# Power_Cell_Lipo_Charger_Booster.net
KiCad netlist of a schematic drawn in EAGLE
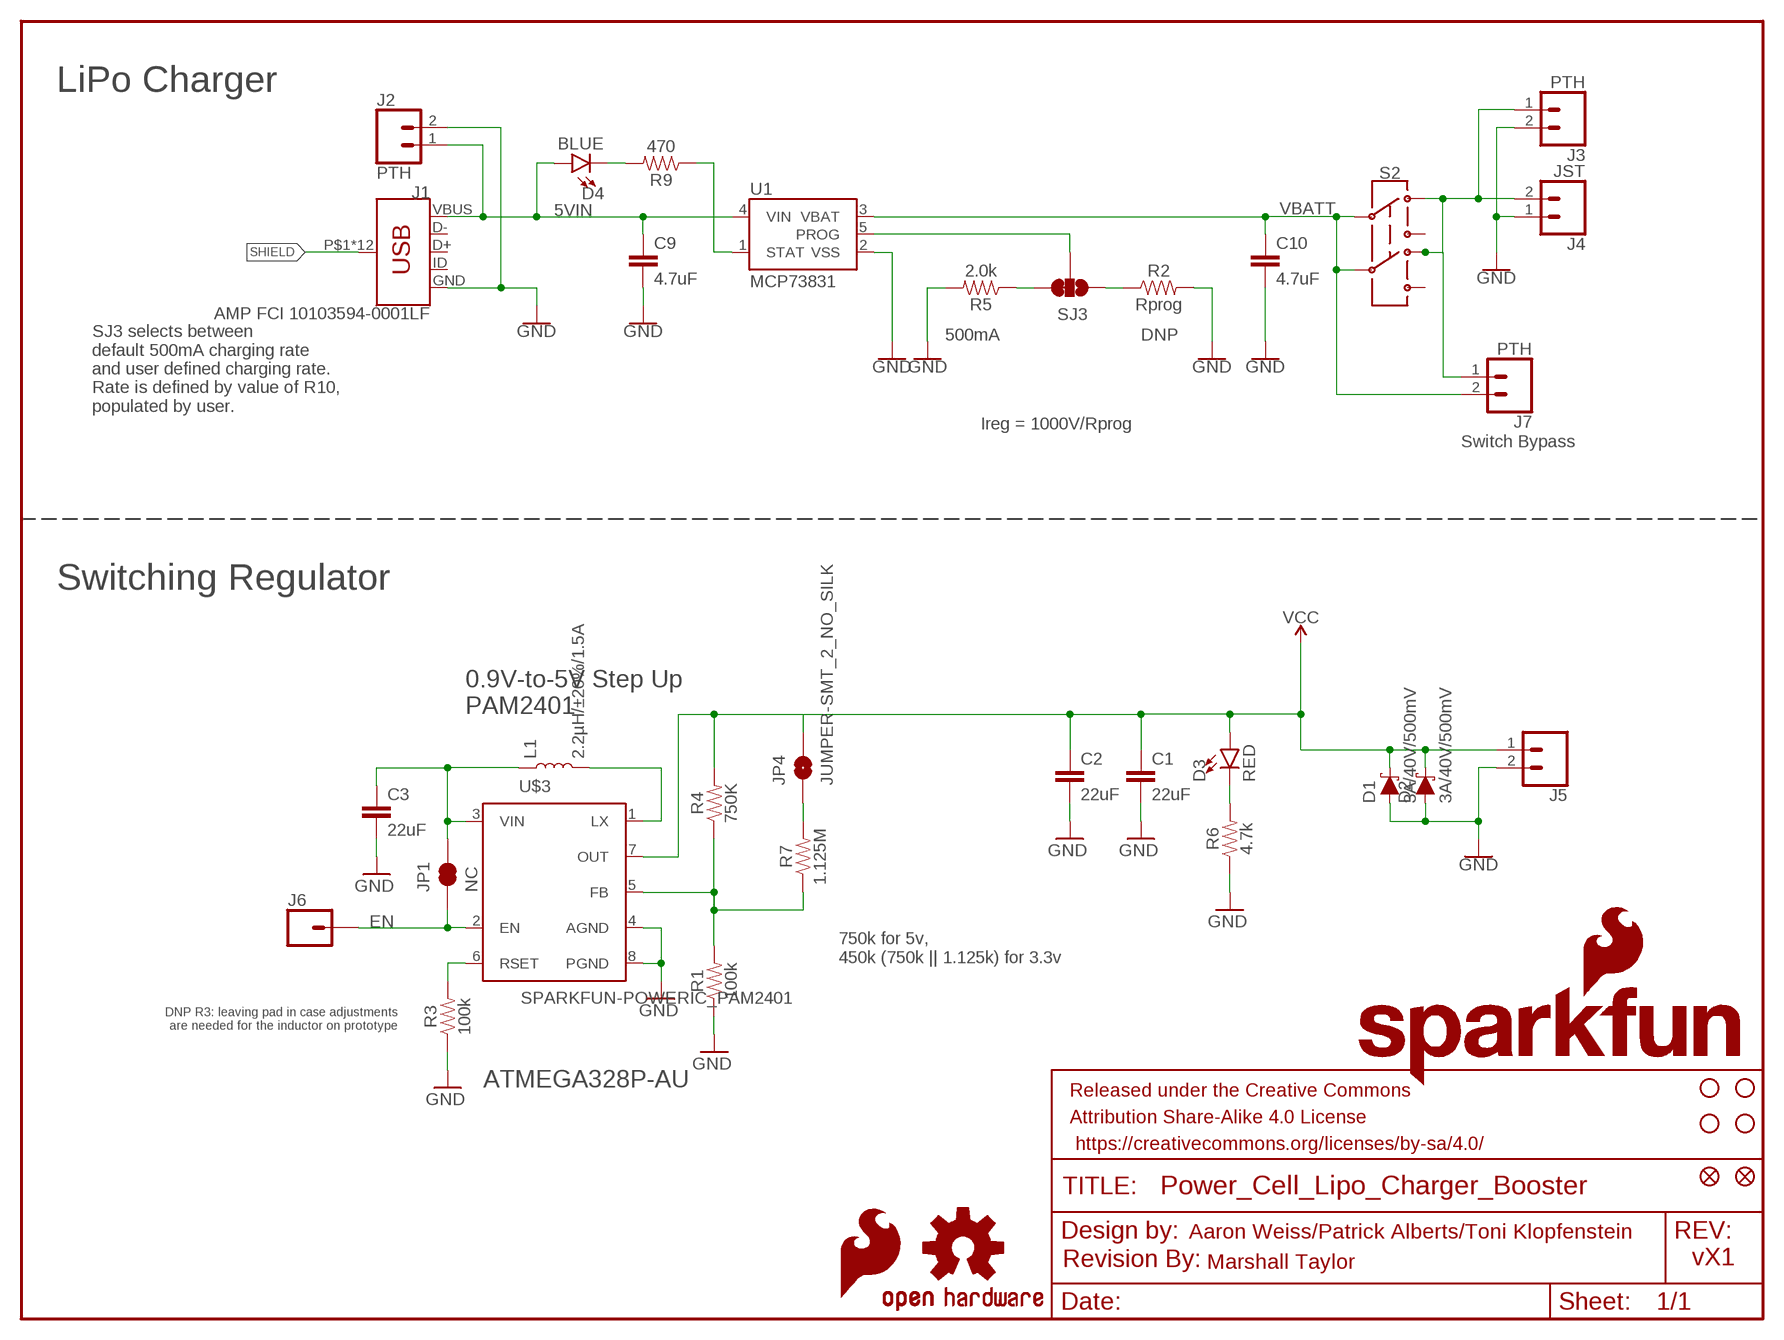
[diagram p0: schematic, sheet 1]

(export (version "E")
  (design (tool "Eeschema 10.0.6"))
  (components
    (comp (ref "C1")
      (value "22uF")
      (footprint "eagle-import:0805")
      (libsource (lib "eagle-import") (part "22UF-0805-6.3V-20%"))
    )
    (comp (ref "C2")
      (value "22uF")
      (footprint "eagle-import:0805")
      (libsource (lib "eagle-import") (part "22UF-0805-6.3V-20%"))
    )
    (comp (ref "C3")
      (value "22uF")
      (footprint "eagle-import:0805")
      (libsource (lib "eagle-import") (part "22UF-0805-6.3V-20%"))
    )
    (comp (ref "C9")
      (value "4.7uF")
      (footprint "eagle-import:0603")
      (libsource (lib "eagle-import") (part "4.7UF0603"))
    )
    (comp (ref "C10")
      (value "4.7uF")
      (footprint "eagle-import:0603")
      (libsource (lib "eagle-import") (part "4.7UF0603"))
    )
    (comp (ref "D1")
      (value "3A/40V/500mV")
      (footprint "eagle-import:SMA-DIODE")
      (libsource (lib "eagle-import") (part "DIODE-SCHOTTKY-B340A"))
    )
    (comp (ref "D2")
      (value "3A/40V/500mV")
      (footprint "eagle-import:SMA-DIODE")
      (libsource (lib "eagle-import") (part "DIODE-SCHOTTKY-B340A"))
    )
    (comp (ref "D3")
      (value "RED")
      (footprint "eagle-import:LED-0603")
      (libsource (lib "eagle-import") (part "LED-RED0603"))
    )
    (comp (ref "D4")
      (value "BLUE")
      (footprint "eagle-import:LED-0603")
      (libsource (lib "eagle-import") (part "LED-BLUE0603"))
    )
    (comp (ref "FRAME1")
      (value "FRAME-LETTER")
      (footprint "eagle-import:CREATIVE_COMMONS")
      (libsource (lib "eagle-import") (part "FRAME-LETTER"))
    )
    (comp (ref "J1")
      (value "AMP FCI 10103594-0001LF")
      (footprint "eagle-import:USB-MICROB-PTH")
      (libsource (lib "eagle-import") (part "USB_MICRO-B_HALF_PTH"))
    )
    (comp (ref "J2")
      (value "PTH")
      (footprint "eagle-import:1X02")
      (libsource (lib "eagle-import") (part "CONN_02"))
    )
    (comp (ref "J3")
      (value "PTH")
      (footprint "eagle-import:1X02")
      (libsource (lib "eagle-import") (part "CONN_02"))
    )
    (comp (ref "J4")
      (value "JST")
      (footprint "eagle-import:JST-2-SMD")
      (libsource (lib "eagle-import") (part "CONN_02-JST-2MM-SMT"))
    )
    (comp (ref "J5")
      (value "CONN_02")
      (footprint "eagle-import:1X02")
      (libsource (lib "eagle-import") (part "CONN_02"))
    )
    (comp (ref "J6")
      (value "CONN_01")
      (footprint "eagle-import:1X01")
      (libsource (lib "eagle-import") (part "CONN_01"))
    )
    (comp (ref "J7")
      (value "PTH")
      (footprint "eagle-import:1X02")
      (libsource (lib "eagle-import") (part "CONN_02"))
    )
    (comp (ref "JP1")
      (value "NC")
      (footprint "eagle-import:SMT-JUMPER_2_NC_TRACE_NO-SILK")
      (libsource (lib "eagle-import") (part "JUMPER-SMT_2_NC_TRACE_NO-SILK"))
    )
    (comp (ref "JP2")
      (value "FIDUCIAL1X2")
      (footprint "eagle-import:FIDUCIAL-1X2")
      (libsource (lib "eagle-import") (part "FIDUCIAL1X2"))
    )
    (comp (ref "JP3")
      (value "SFE_LOGO_NAME_FLAME.1_INCH")
      (footprint "eagle-import:SFE_LOGO_NAME_FLAME_.1")
      (libsource (lib "eagle-import") (part "SFE_LOGO_NAME_FLAME.1_INCH"))
    )
    (comp (ref "JP4")
      (value "JUMPER-SMT_2_NO_SILK")
      (footprint "eagle-import:SMT-JUMPER_2_NO_SILK")
      (libsource (lib "eagle-import") (part "JUMPER-SMT_2_NO_SILK"))
    )
    (comp (ref "JP5")
      (value "STAND-OFF")
      (footprint "eagle-import:STAND-OFF")
      (libsource (lib "eagle-import") (part "STAND-OFF"))
    )
    (comp (ref "JP6")
      (value "STAND-OFF")
      (footprint "eagle-import:STAND-OFF")
      (libsource (lib "eagle-import") (part "STAND-OFF"))
    )
    (comp (ref "JP7")
      (value "STAND-OFF")
      (footprint "eagle-import:STAND-OFF")
      (libsource (lib "eagle-import") (part "STAND-OFF"))
    )
    (comp (ref "JP8")
      (value "STAND-OFF")
      (footprint "eagle-import:STAND-OFF")
      (libsource (lib "eagle-import") (part "STAND-OFF"))
    )
    (comp (ref "JP16")
      (value "FIDUCIAL1X2")
      (footprint "eagle-import:FIDUCIAL-1X2")
      (libsource (lib "eagle-import") (part "FIDUCIAL1X2"))
    )
    (comp (ref "L1")
      (value "2.2µH/±20%/1.5A")
      (footprint "eagle-import:INDUCTOR_2.2UHCOPY")
      (libsource (lib "eagle-import") (part "INDUCTORCOPY-VLF4012AT-2.2UH"))
    )
    (comp (ref "LOGO1")
      (value "SFE_LOGO_FLAME.1_INCH")
      (footprint "eagle-import:SFE_LOGO_FLAME_.1")
      (libsource (lib "eagle-import") (part "SFE_LOGO_FLAME.1_INCH"))
    )
    (comp (ref "R1")
      (value "100k")
      (footprint "eagle-import:0603")
      (libsource (lib "eagle-import") (part "100KOHM-0603-1/10W-1%"))
    )
    (comp (ref "R2")
      (value "Rprog")
      (footprint "eagle-import:0805")
      (libsource (lib "eagle-import") (part "0.75OHM-0805-1/4W-1%"))
    )
    (comp (ref "R3")
      (value "100k")
      (footprint "eagle-import:0603")
      (libsource (lib "eagle-import") (part "100KOHM-0603-1/10W-1%"))
    )
    (comp (ref "R4")
      (value "750K")
      (footprint "eagle-import:0603")
      (libsource (lib "eagle-import") (part "750OHM-0603-1/10W-1%"))
    )
    (comp (ref "R5")
      (value "2.0k")
      (footprint "eagle-import:0603")
      (libsource (lib "eagle-import") (part "2.0KOHM-0603-1/10W-5%"))
    )
    (comp (ref "R6")
      (value "4.7k")
      (footprint "eagle-import:0603")
      (libsource (lib "eagle-import") (part "4.7KOHM-0603-1/10W-1%"))
    )
    (comp (ref "R7")
      (value "1.125M")
      (footprint "eagle-import:0603")
      (libsource (lib "eagle-import") (part "750OHM-0603-1/10W-1%"))
    )
    (comp (ref "R9")
      (value "470")
      (footprint "eagle-import:0603")
      (libsource (lib "eagle-import") (part "470OHM-0603-1/10W-1%"))
    )
    (comp (ref "S2")
      (value "SWITCH-DPDT-SMD-AYZ0202")
      (footprint "eagle-import:SWITCH_DPDT_SMD_AYZ0202")
      (libsource (lib "eagle-import") (part "SWITCH-DPDT-SMD-AYZ0202"))
    )
    (comp (ref "SJ3")
      (value "JUMPER-PAD-3-2OF3_NC_BY_TRACE_SMALL")
      (footprint "eagle-import:PAD-JUMPER-3-2OF3_NC_BY_TRACE_YES_SILK_FULL_BOX")
      (libsource (lib "eagle-import") (part "JUMPER-PAD-3-2OF3_NC_BY_TRACE_SMALL"))
    )
    (comp (ref "U$1")
      (value "OSHW-LOGOS")
      (footprint "eagle-import:OSHW-LOGO-S")
      (libsource (lib "eagle-import") (part "OSHW-LOGOS"))
    )
    (comp (ref "U$2")
      (value "REVISION")
      (footprint "eagle-import:REVISION")
      (libsource (lib "eagle-import") (part "REVISION"))
    )
    (comp (ref "U$3")
      (value "SPARKFUN-POWERIC_PAM2401")
      (footprint "eagle-import:SPARKFUN-POWERIC_MSOP8")
      (libsource (lib "eagle-import") (part "SPARKFUN-POWERIC_PAM2401"))
    )
    (comp (ref "U1")
      (value "MCP73831")
      (footprint "eagle-import:SOT23-5")
      (libsource (lib "eagle-import") (part "MCP73831"))
    )
  )
  (nets
    (net (code "1") (name "/5VIN") (class "Default")
      (node (ref "C9") (pin "1") (pinfunction "1_1") (pintype "passive"))
      (node (ref "D4") (pin "A") (pinfunction "A_A") (pintype "passive"))
      (node (ref "J1") (pin "VBUS") (pinfunction "VBUS_VBUS") (pintype "power_in"))
      (node (ref "J2") (pin "1") (pinfunction "1_1") (pintype "passive"))
      (node (ref "U1") (pin "4") (pinfunction "VIN_4") (pintype "power_in"))
    )
    (net (code "2") (name "/EN") (class "Default")
      (node (ref "J6") (pin "1") (pinfunction "1_1") (pintype "passive"))
      (node (ref "JP1") (pin "1") (pinfunction "1_1") (pintype "passive"))
      (node (ref "U$3") (pin "2") (pinfunction "EN_2") (pintype "bidirectional"))
    )
    (net (code "3") (name "/VBATT") (class "Default")
      (node (ref "C10") (pin "1") (pinfunction "1_1") (pintype "passive"))
      (node (ref "C3") (pin "1") (pinfunction "1_1") (pintype "passive"))
      (node (ref "J7") (pin "2") (pinfunction "2_2") (pintype "passive"))
      (node (ref "JP1") (pin "2") (pinfunction "2_2") (pintype "passive"))
      (node (ref "L1") (pin "P$1") (pinfunction "1_P$1") (pintype "passive"))
      (node (ref "S2") (pin "2") (pinfunction "2_2") (pintype "bidirectional"))
      (node (ref "S2") (pin "5") (pinfunction "5_5") (pintype "bidirectional"))
      (node (ref "U$3") (pin "3") (pinfunction "VIN_3") (pintype "bidirectional"))
      (node (ref "U1") (pin "3") (pinfunction "VBAT_3") (pintype "power_in"))
    )
    (net (code "4") (name "GND") (class "Default")
      (node (ref "C1") (pin "2") (pinfunction "2_2") (pintype "passive"))
      (node (ref "C10") (pin "2") (pinfunction "2_2") (pintype "passive"))
      (node (ref "C2") (pin "2") (pinfunction "2_2") (pintype "passive"))
      (node (ref "C3") (pin "2") (pinfunction "2_2") (pintype "passive"))
      (node (ref "C9") (pin "2") (pinfunction "2_2") (pintype "passive"))
      (node (ref "D1") (pin "A") (pinfunction "A_A") (pintype "passive"))
      (node (ref "D2") (pin "A") (pinfunction "A_A") (pintype "passive"))
      (node (ref "J1") (pin "GND") (pinfunction "GND_GND") (pintype "power_in"))
      (node (ref "J2") (pin "2") (pinfunction "2_2") (pintype "passive"))
      (node (ref "J3") (pin "2") (pinfunction "2_2") (pintype "passive"))
      (node (ref "J4") (pin "1") (pinfunction "2_1") (pintype "passive"))
      (node (ref "J5") (pin "2") (pinfunction "2_2") (pintype "passive"))
      (node (ref "R1") (pin "1") (pinfunction "1_1") (pintype "passive"))
      (node (ref "R2") (pin "2") (pinfunction "2_2") (pintype "passive"))
      (node (ref "R3") (pin "1") (pinfunction "1_1") (pintype "passive"))
      (node (ref "R5") (pin "2") (pinfunction "2_2") (pintype "passive"))
      (node (ref "R6") (pin "1") (pinfunction "1_1") (pintype "passive"))
      (node (ref "U$3") (pin "4") (pinfunction "AGND_4") (pintype "bidirectional"))
      (node (ref "U$3") (pin "8") (pinfunction "PGND_8") (pintype "bidirectional"))
      (node (ref "U1") (pin "2") (pinfunction "VSS_2") (pintype "power_in"))
    )
    (net (code "5") (name "Net-(D3-PadC)") (class "Default")
      (node (ref "D3") (pin "C") (pinfunction "C_C") (pintype "passive"))
      (node (ref "R6") (pin "2") (pinfunction "2_2") (pintype "passive"))
    )
    (net (code "6") (name "Net-(D4-PadC)") (class "Default")
      (node (ref "D4") (pin "C") (pinfunction "C_C") (pintype "passive"))
      (node (ref "R9") (pin "2") (pinfunction "2_2") (pintype "passive"))
    )
    (net (code "7") (name "Net-(J4-1)") (class "Default")
      (node (ref "J3") (pin "1") (pinfunction "1_1") (pintype "passive"))
      (node (ref "J4") (pin "2") (pinfunction "1_2") (pintype "passive"))
      (node (ref "J7") (pin "1") (pinfunction "1_1") (pintype "passive"))
      (node (ref "S2") (pin "1") (pinfunction "1_1") (pintype "bidirectional"))
      (node (ref "S2") (pin "4") (pinfunction "4_4") (pintype "bidirectional"))
    )
    (net (code "8") (name "Net-(JP4-Pad1)") (class "Default")
      (node (ref "JP4") (pin "1") (pinfunction "1_1") (pintype "passive"))
      (node (ref "R7") (pin "2") (pinfunction "2_2") (pintype "passive"))
    )
    (net (code "9") (name "Net-(L1-2)") (class "Default")
      (node (ref "L1") (pin "P$2") (pinfunction "2_P$2") (pintype "passive"))
      (node (ref "U$3") (pin "1") (pinfunction "LX_1") (pintype "bidirectional"))
    )
    (net (code "10") (name "Net-(R2-Pad1)") (class "Default")
      (node (ref "R2") (pin "1") (pinfunction "1_1") (pintype "passive"))
      (node (ref "SJ3") (pin "1") (pinfunction "1_1") (pintype "passive"))
    )
    (net (code "11") (name "Net-(R5-Pad1)") (class "Default")
      (node (ref "R5") (pin "1") (pinfunction "1_1") (pintype "passive"))
      (node (ref "SJ3") (pin "3") (pinfunction "3_3") (pintype "passive"))
    )
    (net (code "12") (name "Net-(U$3-FB)") (class "Default")
      (node (ref "R1") (pin "2") (pinfunction "2_2") (pintype "passive"))
      (node (ref "R4") (pin "1") (pinfunction "1_1") (pintype "passive"))
      (node (ref "R7") (pin "1") (pinfunction "1_1") (pintype "passive"))
      (node (ref "U$3") (pin "5") (pinfunction "FB_5") (pintype "bidirectional"))
    )
    (net (code "13") (name "Net-(U$3-RSET)") (class "Default")
      (node (ref "R3") (pin "2") (pinfunction "2_2") (pintype "passive"))
      (node (ref "U$3") (pin "6") (pinfunction "RSET_6") (pintype "bidirectional"))
    )
    (net (code "14") (name "Net-(U1-PROG)") (class "Default")
      (node (ref "SJ3") (pin "2") (pinfunction "2_2") (pintype "passive"))
      (node (ref "U1") (pin "5") (pinfunction "PROG_5") (pintype "input"))
    )
    (net (code "15") (name "Net-(U1-STAT)") (class "Default")
      (node (ref "R9") (pin "1") (pinfunction "1_1") (pintype "passive"))
      (node (ref "U1") (pin "1") (pinfunction "STAT_1") (pintype "output"))
    )
    (net (code "16") (name "SHIELD") (class "Default")
      (node (ref "J1") (pin "P$1") (pinfunction "SHIELD_P$1") (pintype "bidirectional"))
      (node (ref "J1") (pin "P$10") (pinfunction "SHIELD_P$10") (pintype "bidirectional"))
      (node (ref "J1") (pin "P$12") (pinfunction "SHIELD_P$12") (pintype "bidirectional"))
      (node (ref "J1") (pin "P$2") (pinfunction "SHIELD_P$2") (pintype "bidirectional"))
      (node (ref "J1") (pin "P$3") (pinfunction "SHIELD_P$3") (pintype "bidirectional"))
      (node (ref "J1") (pin "P$4") (pinfunction "SHIELD_P$4") (pintype "bidirectional"))
      (node (ref "J1") (pin "P$6") (pinfunction "SHIELD_P$6") (pintype "bidirectional"))
      (node (ref "J1") (pin "P$8") (pinfunction "SHIELD_P$8") (pintype "bidirectional"))
      (node (ref "J1") (pin "SHEILD2") (pinfunction "SHIELD_SHEILD2") (pintype "bidirectional"))
      (node (ref "J1") (pin "SHIELD") (pinfunction "SHIELD_SHIELD") (pintype "bidirectional"))
      (node (ref "J1") (pin "SHIELD3") (pinfunction "SHIELD_SHIELD3") (pintype "bidirectional"))
      (node (ref "J1") (pin "SHIELD4") (pinfunction "SHIELD_SHIELD4") (pintype "bidirectional"))
    )
    (net (code "17") (name "VCC") (class "Default")
      (node (ref "C1") (pin "1") (pinfunction "1_1") (pintype "passive"))
      (node (ref "C2") (pin "1") (pinfunction "1_1") (pintype "passive"))
      (node (ref "D1") (pin "C") (pinfunction "C_C") (pintype "passive"))
      (node (ref "D2") (pin "C") (pinfunction "C_C") (pintype "passive"))
      (node (ref "D3") (pin "A") (pinfunction "A_A") (pintype "passive"))
      (node (ref "J5") (pin "1") (pinfunction "1_1") (pintype "passive"))
      (node (ref "JP4") (pin "2") (pinfunction "2_2") (pintype "passive"))
      (node (ref "R4") (pin "2") (pinfunction "2_2") (pintype "passive"))
      (node (ref "U$3") (pin "7") (pinfunction "OUT_7") (pintype "bidirectional"))
    )
    (net (code "18") (name "unconnected-(J1-PadD+)") (class "Default")
      (node (ref "J1") (pin "D+") (pinfunction "D+_D+") (pintype "bidirectional"))
    )
    (net (code "19") (name "unconnected-(J1-PadD-)") (class "Default")
      (node (ref "J1") (pin "D-") (pinfunction "D-_D-") (pintype "bidirectional"))
    )
    (net (code "20") (name "unconnected-(J1-PadID)") (class "Default")
      (node (ref "J1") (pin "ID") (pinfunction "ID_ID") (pintype "bidirectional"))
    )
    (net (code "21") (name "unconnected-(S2-Pad3)") (class "Default")
      (node (ref "S2") (pin "3") (pinfunction "3_3") (pintype "bidirectional"))
    )
    (net (code "22") (name "unconnected-(S2-Pad6)") (class "Default")
      (node (ref "S2") (pin "6") (pinfunction "6_6") (pintype "bidirectional"))
    )
  )
)
